# module-simple.net
KiCad netlist of a schematic drawn in EAGLE
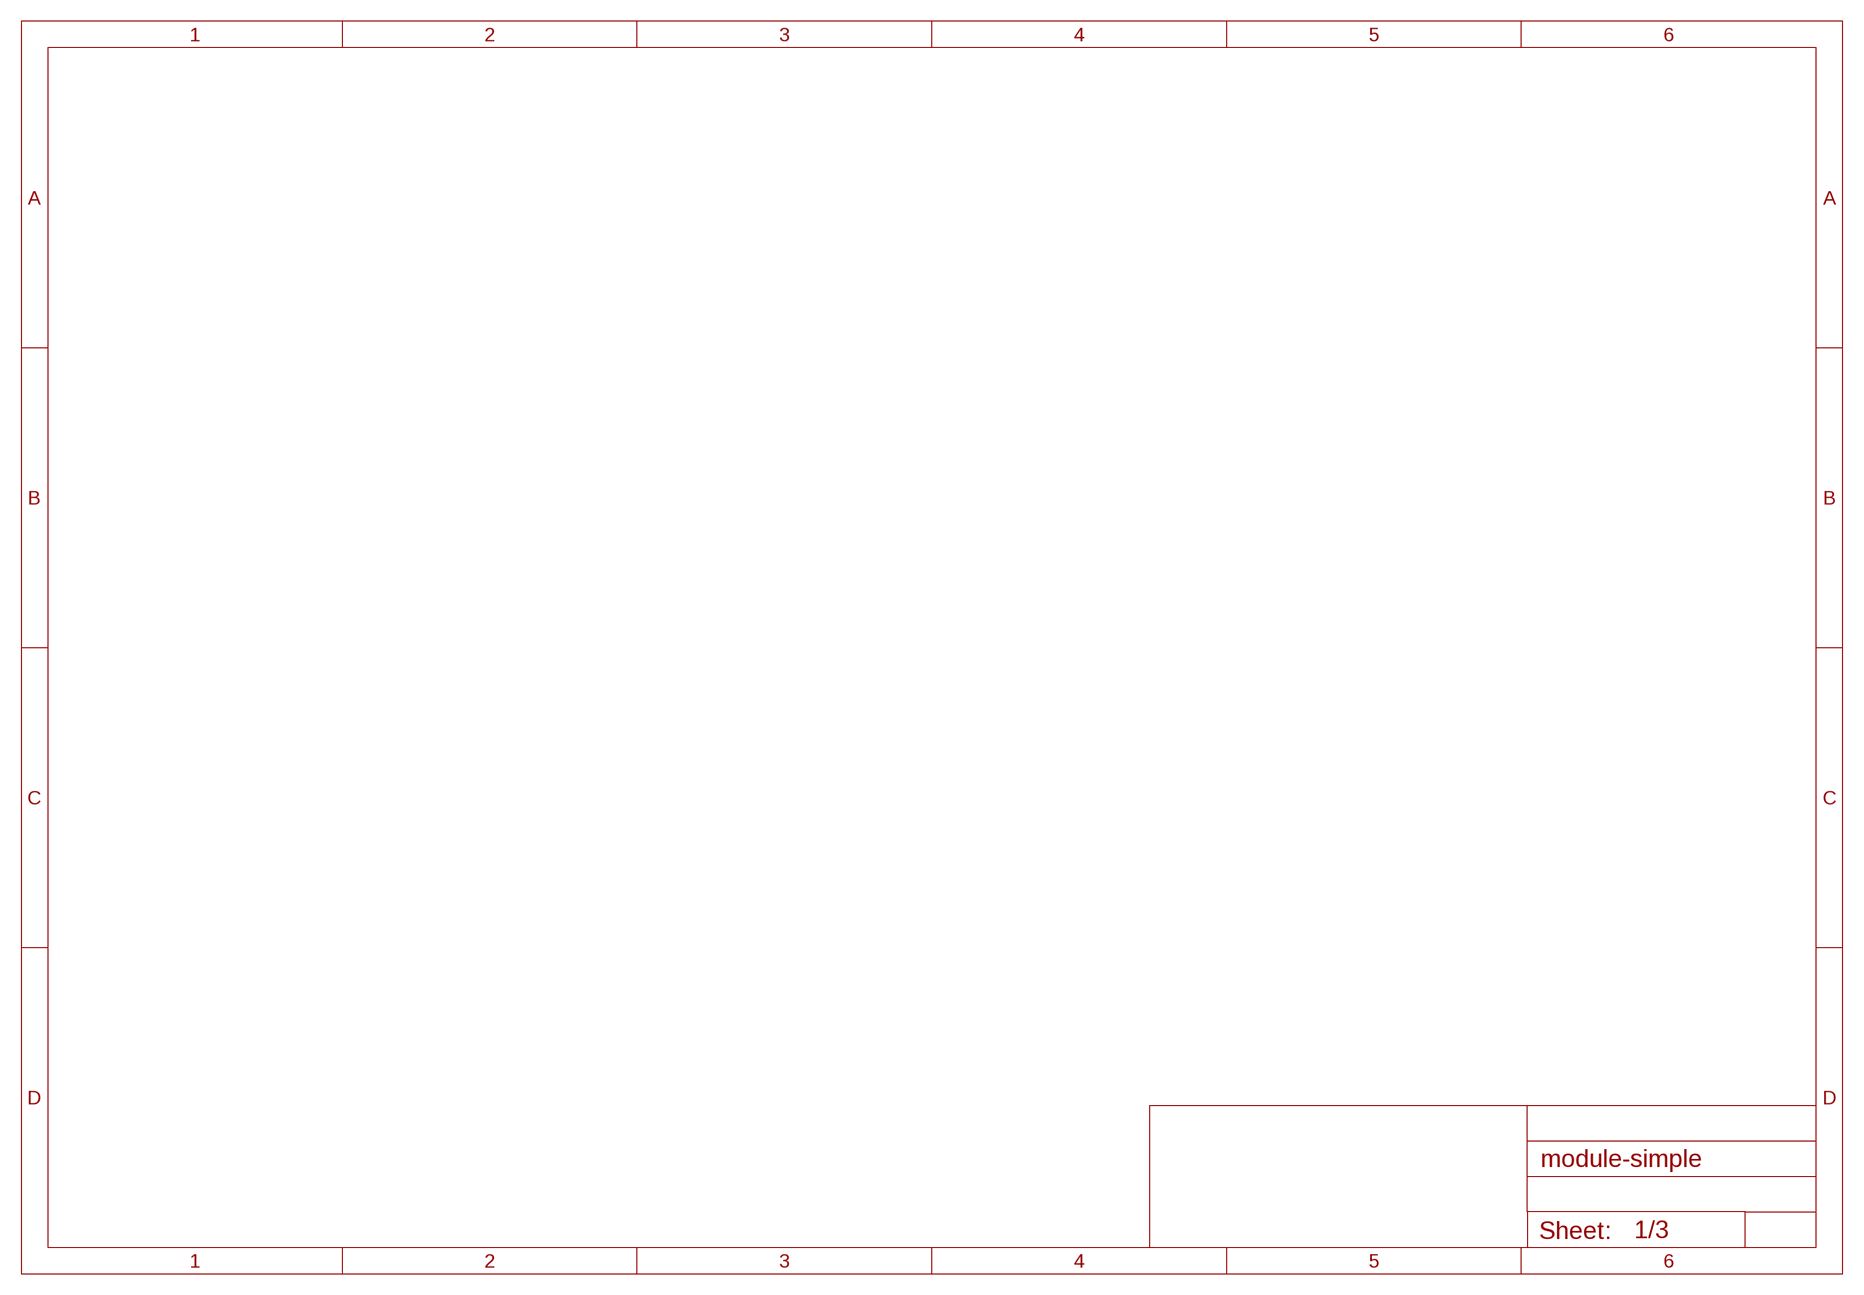
[diagram p0: schematic, sheet 1]
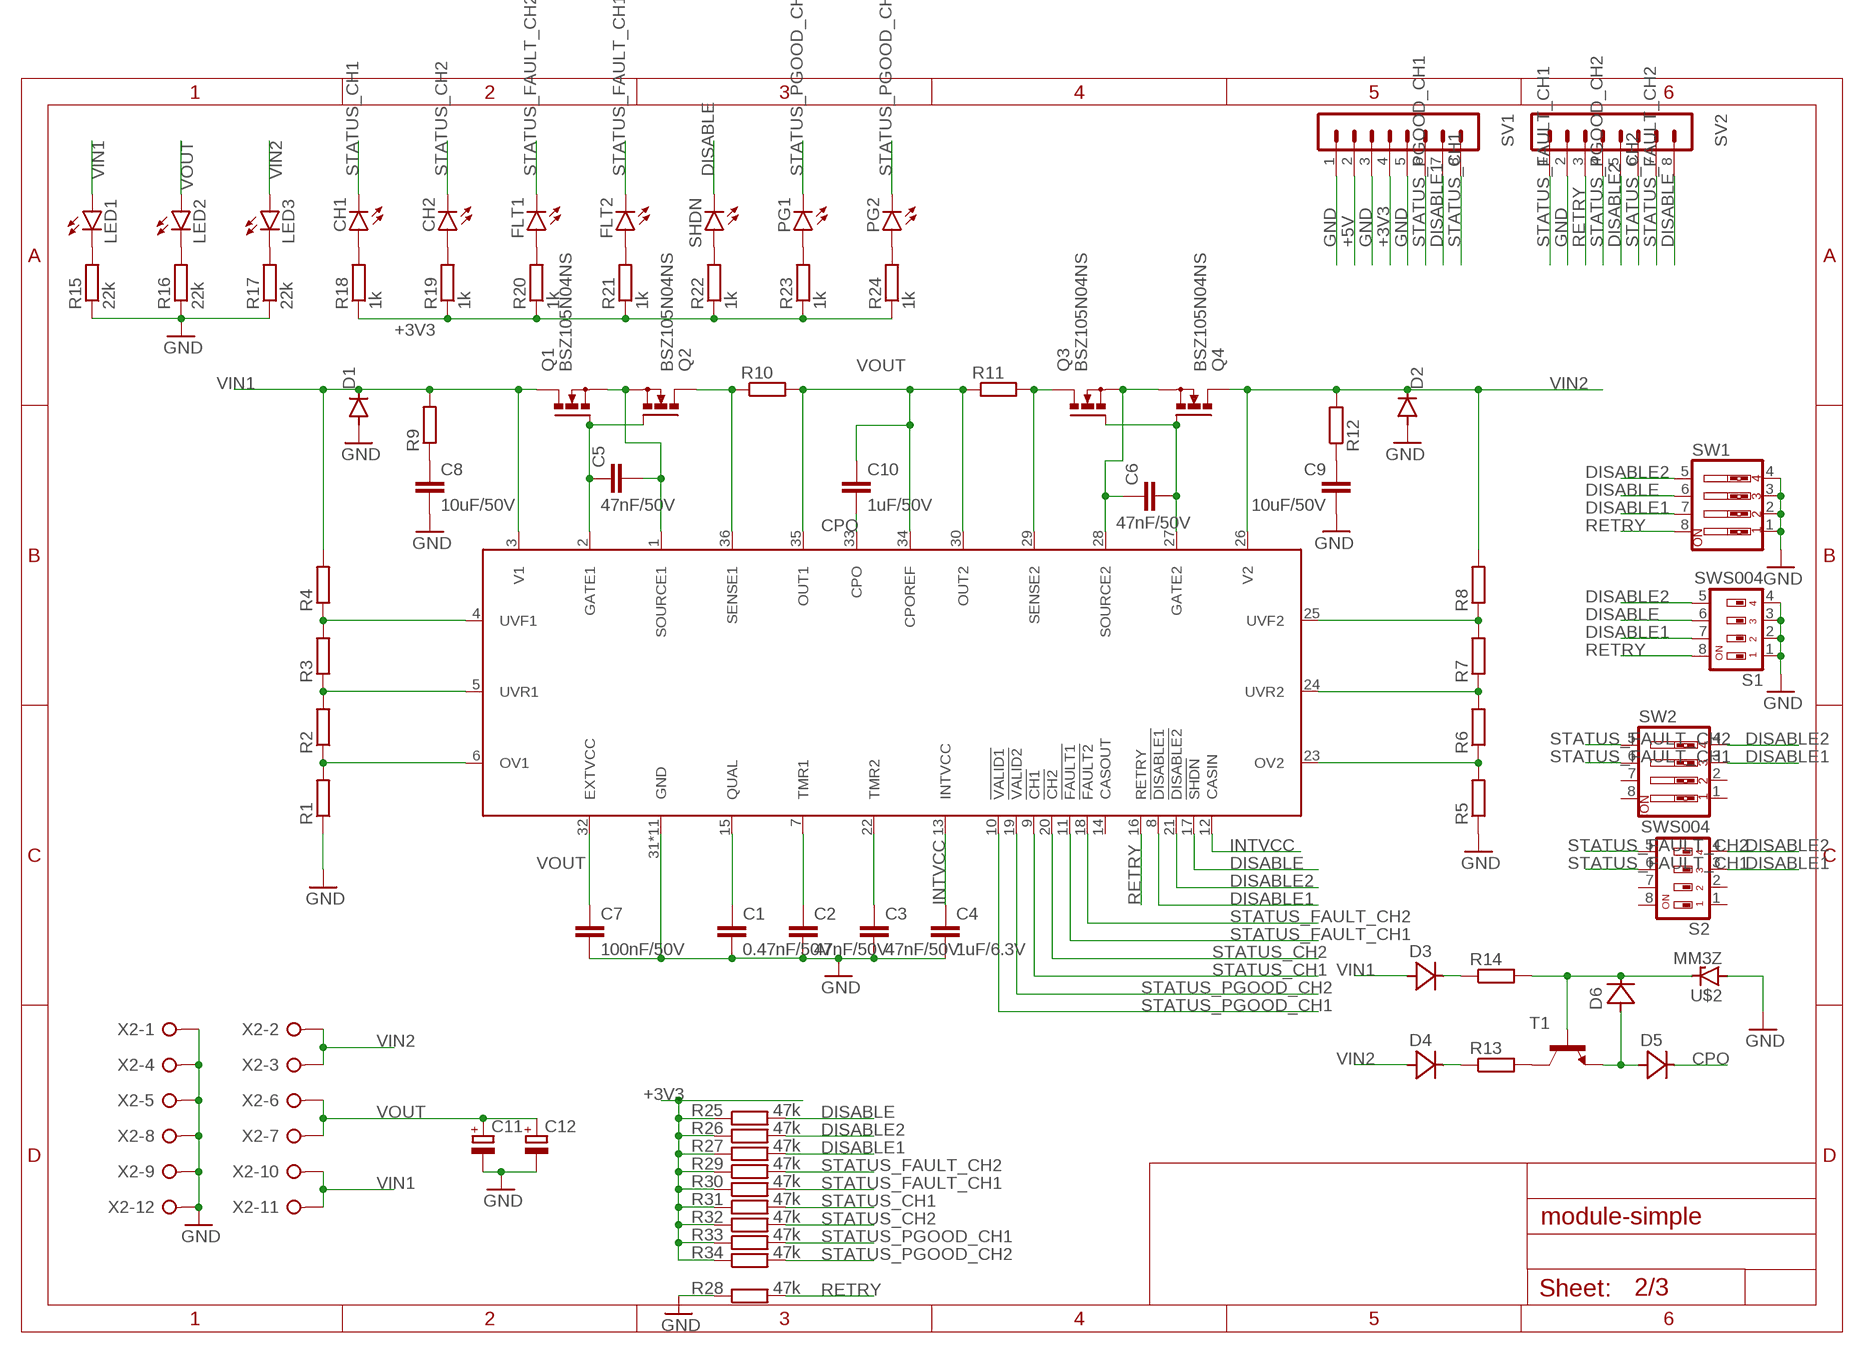
[diagram p1: schematic, sheet 2]
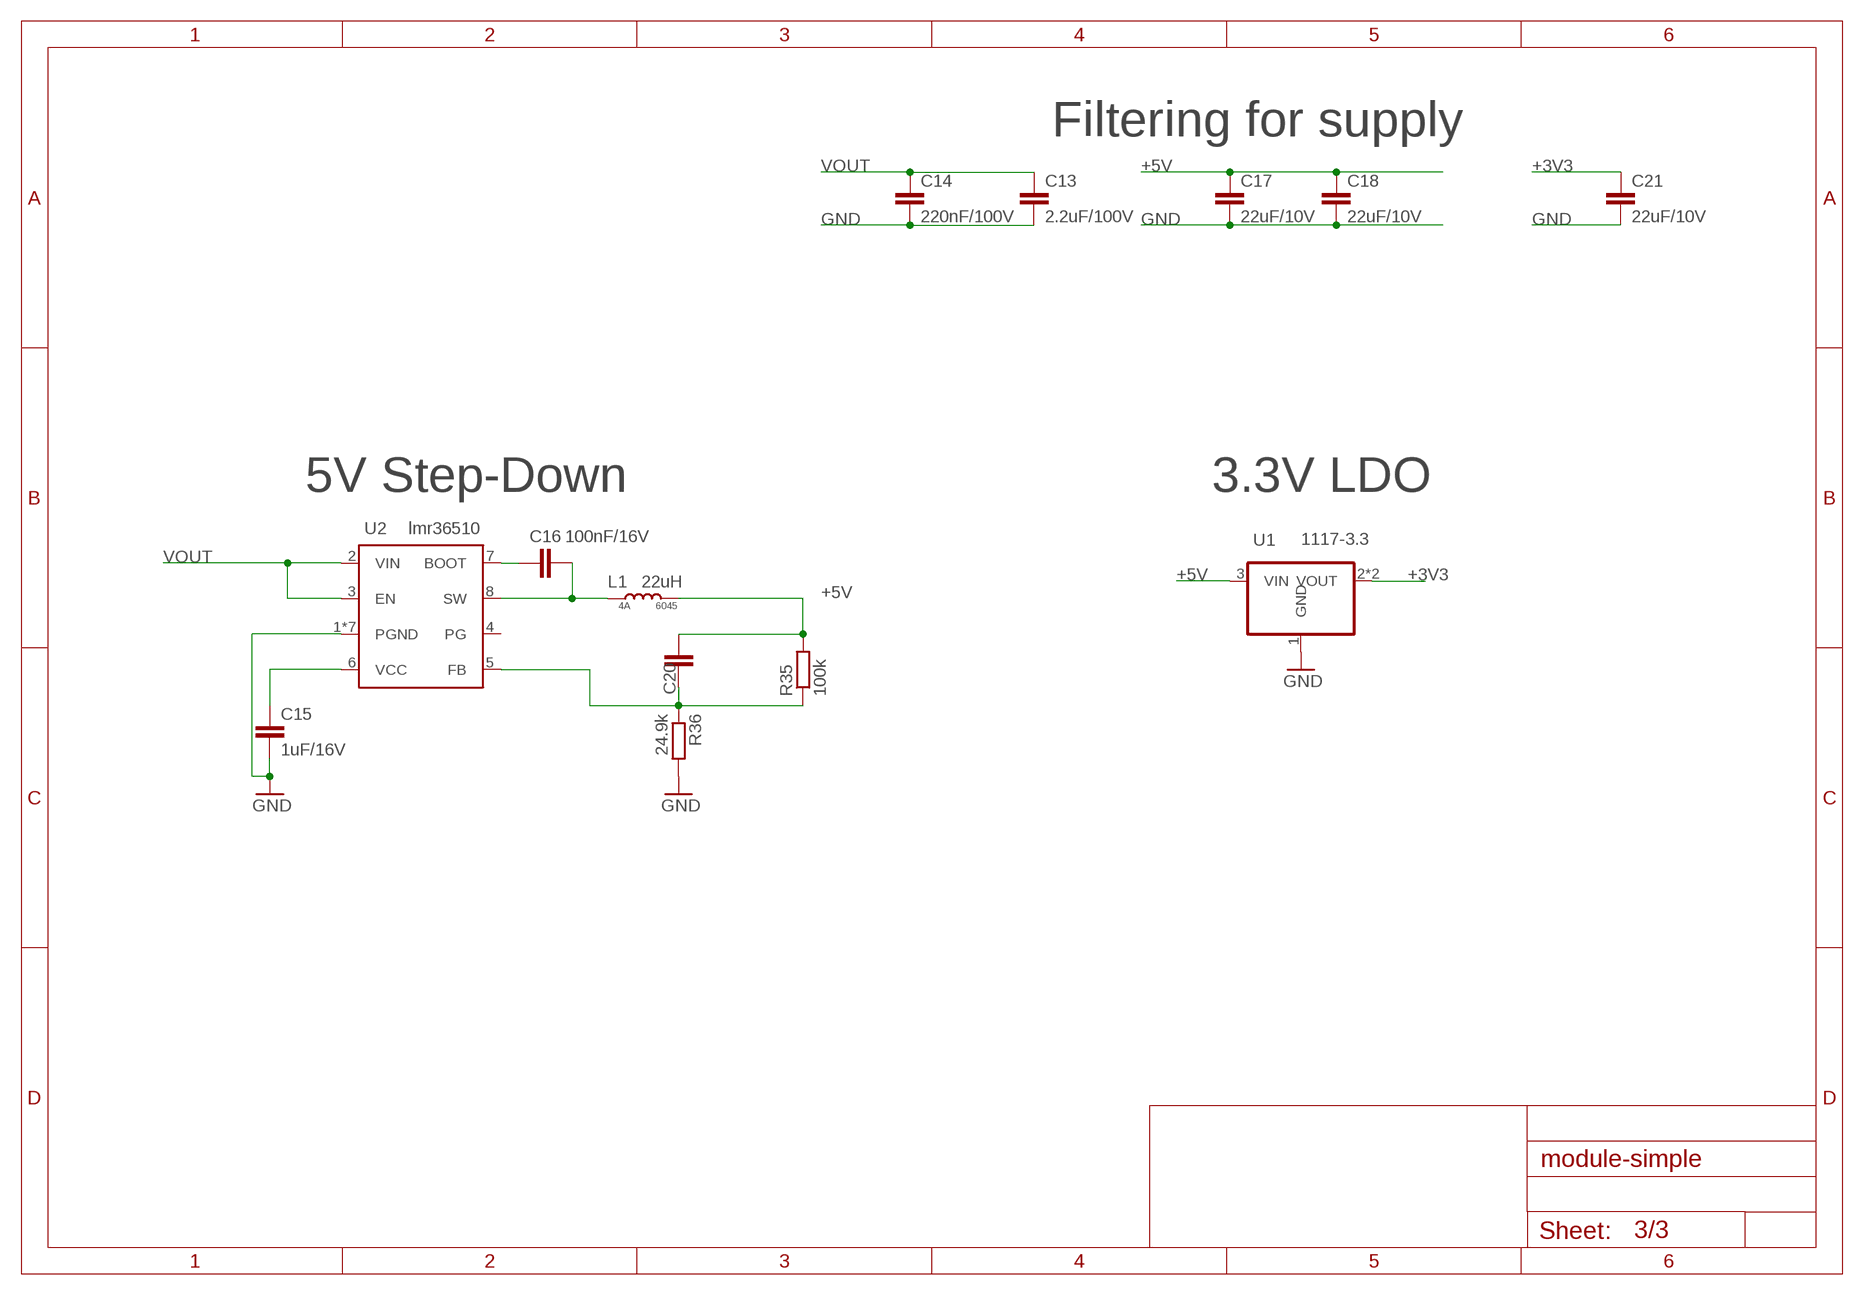
[diagram p2: schematic, sheet 3]

(export (version "E")
  (design (tool "Eeschema 10.0.6"))
  (components
    (comp (ref "C1")
      (value "0.47nF/50V")
      (footprint "eagle-import:C0603")
      (libsource (lib "eagle-import") (part "C-EUC0603"))
    )
    (comp (ref "C2")
      (value "47nF/50V")
      (footprint "eagle-import:C0603")
      (libsource (lib "eagle-import") (part "C-EUC0603"))
    )
    (comp (ref "C3")
      (value "47nF/50V")
      (footprint "eagle-import:C0603")
      (libsource (lib "eagle-import") (part "C-EUC0603"))
    )
    (comp (ref "C4")
      (value "1uF/6.3V")
      (footprint "eagle-import:C0603")
      (libsource (lib "eagle-import") (part "C-EUC0603"))
    )
    (comp (ref "C5")
      (value "47nF/50V")
      (footprint "eagle-import:C0603")
      (libsource (lib "eagle-import") (part "C-EUC0603"))
    )
    (comp (ref "C6")
      (value "47nF/50V")
      (footprint "eagle-import:C0603")
      (libsource (lib "eagle-import") (part "C-EUC0603"))
    )
    (comp (ref "C7")
      (value "100nF/50V")
      (footprint "eagle-import:C0603")
      (libsource (lib "eagle-import") (part "C-EUC0603"))
    )
    (comp (ref "C8")
      (value "10uF/50V")
      (footprint "eagle-import:C1206")
      (libsource (lib "eagle-import") (part "C-EUC1206"))
    )
    (comp (ref "C9")
      (value "10uF/50V")
      (footprint "eagle-import:C1206")
      (libsource (lib "eagle-import") (part "C-EUC1206"))
    )
    (comp (ref "C10")
      (value "1uF/50V")
      (footprint "eagle-import:C0805")
      (libsource (lib "eagle-import") (part "C-EUC0805"))
    )
    (comp (ref "C11")
      (value "CPOL-EU140CLH-1010")
      (footprint "eagle-import:140CLH-1010")
      (libsource (lib "eagle-import") (part "CPOL-EU140CLH-1010"))
    )
    (comp (ref "C12")
      (value "CPOL-EU140CLH-1010")
      (footprint "eagle-import:140CLH-1010")
      (libsource (lib "eagle-import") (part "CPOL-EU140CLH-1010"))
    )
    (comp (ref "CH1")
      (value "LEDCHIP-LED0603")
      (footprint "eagle-import:CHIP-LED0603")
      (libsource (lib "eagle-import") (part "LEDCHIP-LED0603"))
    )
    (comp (ref "CH2")
      (value "LEDCHIP-LED0603")
      (footprint "eagle-import:CHIP-LED0603")
      (libsource (lib "eagle-import") (part "LEDCHIP-LED0603"))
    )
    (comp (ref "D1")
      (value "DIODE-DO214AC")
      (footprint "eagle-import:DO214AC")
      (libsource (lib "eagle-import") (part "DIODE-DO214AC"))
    )
    (comp (ref "D2")
      (value "DIODE-DO214AC")
      (footprint "eagle-import:DO214AC")
      (libsource (lib "eagle-import") (part "DIODE-DO214AC"))
    )
    (comp (ref "D3")
      (value "1N4148WS")
      (footprint "eagle-import:SOD323")
      (libsource (lib "eagle-import") (part "1N4148WS"))
    )
    (comp (ref "D4")
      (value "1N4148WS")
      (footprint "eagle-import:SOD323")
      (libsource (lib "eagle-import") (part "1N4148WS"))
    )
    (comp (ref "D5")
      (value "1N4148WS")
      (footprint "eagle-import:SOD323")
      (libsource (lib "eagle-import") (part "1N4148WS"))
    )
    (comp (ref "D6")
      (value "1N4148WS")
      (footprint "eagle-import:SOD323")
      (libsource (lib "eagle-import") (part "1N4148WS"))
    )
    (comp (ref "FLT1")
      (value "LEDCHIP-LED0603")
      (footprint "eagle-import:CHIP-LED0603")
      (libsource (lib "eagle-import") (part "LEDCHIP-LED0603"))
    )
    (comp (ref "FLT2")
      (value "LEDCHIP-LED0603")
      (footprint "eagle-import:CHIP-LED0603")
      (libsource (lib "eagle-import") (part "LEDCHIP-LED0603"))
    )
    (comp (ref "LED1")
      (value "LEDCHIP-LED0603")
      (footprint "eagle-import:CHIP-LED0603")
      (libsource (lib "eagle-import") (part "LEDCHIP-LED0603"))
    )
    (comp (ref "LED2")
      (value "LEDCHIP-LED0603")
      (footprint "eagle-import:CHIP-LED0603")
      (libsource (lib "eagle-import") (part "LEDCHIP-LED0603"))
    )
    (comp (ref "LED3")
      (value "LEDCHIP-LED0603")
      (footprint "eagle-import:CHIP-LED0603")
      (libsource (lib "eagle-import") (part "LEDCHIP-LED0603"))
    )
    (comp (ref "PG1")
      (value "LEDCHIP-LED0603")
      (footprint "eagle-import:CHIP-LED0603")
      (libsource (lib "eagle-import") (part "LEDCHIP-LED0603"))
    )
    (comp (ref "PG2")
      (value "LEDCHIP-LED0603")
      (footprint "eagle-import:CHIP-LED0603")
      (libsource (lib "eagle-import") (part "LEDCHIP-LED0603"))
    )
    (comp (ref "Q1")
      (value "BSZ105N04NS")
      (footprint "eagle-import:PG-TDSON-8")
      (libsource (lib "eagle-import") (part "BSZ105N04NS"))
    )
    (comp (ref "Q2")
      (value "BSZ105N04NS")
      (footprint "eagle-import:PG-TDSON-8")
      (libsource (lib "eagle-import") (part "BSZ105N04NS"))
    )
    (comp (ref "Q3")
      (value "BSZ105N04NS")
      (footprint "eagle-import:PG-TDSON-8")
      (libsource (lib "eagle-import") (part "BSZ105N04NS"))
    )
    (comp (ref "Q4")
      (value "BSZ105N04NS")
      (footprint "eagle-import:PG-TDSON-8")
      (libsource (lib "eagle-import") (part "BSZ105N04NS"))
    )
    (comp (ref "R1")
      (value "R-EU_R0603")
      (footprint "eagle-import:R0603")
      (libsource (lib "eagle-import") (part "R-EU_R0603"))
    )
    (comp (ref "R2")
      (value "R-EU_R0603")
      (footprint "eagle-import:R0603")
      (libsource (lib "eagle-import") (part "R-EU_R0603"))
    )
    (comp (ref "R3")
      (value "R-EU_R0603")
      (footprint "eagle-import:R0603")
      (libsource (lib "eagle-import") (part "R-EU_R0603"))
    )
    (comp (ref "R4")
      (value "R-EU_R0603")
      (footprint "eagle-import:R0603")
      (libsource (lib "eagle-import") (part "R-EU_R0603"))
    )
    (comp (ref "R5")
      (value "R-EU_R0603")
      (footprint "eagle-import:R0603")
      (libsource (lib "eagle-import") (part "R-EU_R0603"))
    )
    (comp (ref "R6")
      (value "R-EU_R0603")
      (footprint "eagle-import:R0603")
      (libsource (lib "eagle-import") (part "R-EU_R0603"))
    )
    (comp (ref "R7")
      (value "R-EU_R0603")
      (footprint "eagle-import:R0603")
      (libsource (lib "eagle-import") (part "R-EU_R0603"))
    )
    (comp (ref "R8")
      (value "R-EU_R0603")
      (footprint "eagle-import:R0603")
      (libsource (lib "eagle-import") (part "R-EU_R0603"))
    )
    (comp (ref "R9")
      (value "R-EU_R0603")
      (footprint "eagle-import:R0603")
      (libsource (lib "eagle-import") (part "R-EU_R0603"))
    )
    (comp (ref "R10")
      (value "R-EU_R2512")
      (footprint "eagle-import:R2512")
      (libsource (lib "eagle-import") (part "R-EU_R2512"))
    )
    (comp (ref "R11")
      (value "R-EU_R2512")
      (footprint "eagle-import:R2512")
      (libsource (lib "eagle-import") (part "R-EU_R2512"))
    )
    (comp (ref "R12")
      (value "R-EU_R0603")
      (footprint "eagle-import:R0603")
      (libsource (lib "eagle-import") (part "R-EU_R0603"))
    )
    (comp (ref "R13")
      (value "R-EU_R0603")
      (footprint "eagle-import:R0603")
      (libsource (lib "eagle-import") (part "R-EU_R0603"))
    )
    (comp (ref "R14")
      (value "R-EU_R0603")
      (footprint "eagle-import:R0603")
      (libsource (lib "eagle-import") (part "R-EU_R0603"))
    )
    (comp (ref "R15")
      (value "22k")
      (footprint "eagle-import:R0603")
      (libsource (lib "eagle-import") (part "R-EU_R0603"))
    )
    (comp (ref "R16")
      (value "22k")
      (footprint "eagle-import:R0603")
      (libsource (lib "eagle-import") (part "R-EU_R0603"))
    )
    (comp (ref "R17")
      (value "22k")
      (footprint "eagle-import:R0603")
      (libsource (lib "eagle-import") (part "R-EU_R0603"))
    )
    (comp (ref "R18")
      (value "1k")
      (footprint "eagle-import:R0603")
      (libsource (lib "eagle-import") (part "R-EU_R0603"))
    )
    (comp (ref "R19")
      (value "1k")
      (footprint "eagle-import:R0603")
      (libsource (lib "eagle-import") (part "R-EU_R0603"))
    )
    (comp (ref "R20")
      (value "1k")
      (footprint "eagle-import:R0603")
      (libsource (lib "eagle-import") (part "R-EU_R0603"))
    )
    (comp (ref "R21")
      (value "1k")
      (footprint "eagle-import:R0603")
      (libsource (lib "eagle-import") (part "R-EU_R0603"))
    )
    (comp (ref "R22")
      (value "1k")
      (footprint "eagle-import:R0603")
      (libsource (lib "eagle-import") (part "R-EU_R0603"))
    )
    (comp (ref "R23")
      (value "1k")
      (footprint "eagle-import:R0603")
      (libsource (lib "eagle-import") (part "R-EU_R0603"))
    )
    (comp (ref "R24")
      (value "1k")
      (footprint "eagle-import:R0603")
      (libsource (lib "eagle-import") (part "R-EU_R0603"))
    )
    (comp (ref "R25")
      (value "47k")
      (footprint "eagle-import:R0603")
      (libsource (lib "eagle-import") (part "R-EU_R0603"))
    )
    (comp (ref "R26")
      (value "47k")
      (footprint "eagle-import:R0603")
      (libsource (lib "eagle-import") (part "R-EU_R0603"))
    )
    (comp (ref "R27")
      (value "47k")
      (footprint "eagle-import:R0603")
      (libsource (lib "eagle-import") (part "R-EU_R0603"))
    )
    (comp (ref "R28")
      (value "47k")
      (footprint "eagle-import:R0603")
      (libsource (lib "eagle-import") (part "R-EU_R0603"))
    )
    (comp (ref "R29")
      (value "47k")
      (footprint "eagle-import:R0603")
      (libsource (lib "eagle-import") (part "R-EU_R0603"))
    )
    (comp (ref "R30")
      (value "47k")
      (footprint "eagle-import:R0603")
      (libsource (lib "eagle-import") (part "R-EU_R0603"))
    )
    (comp (ref "R31")
      (value "47k")
      (footprint "eagle-import:R0603")
      (libsource (lib "eagle-import") (part "R-EU_R0603"))
    )
    (comp (ref "R32")
      (value "47k")
      (footprint "eagle-import:R0603")
      (libsource (lib "eagle-import") (part "R-EU_R0603"))
    )
    (comp (ref "R33")
      (value "47k")
      (footprint "eagle-import:R0603")
      (libsource (lib "eagle-import") (part "R-EU_R0603"))
    )
    (comp (ref "R34")
      (value "47k")
      (footprint "eagle-import:R0603")
      (libsource (lib "eagle-import") (part "R-EU_R0603"))
    )
    (comp (ref "S1")
      (value "SWS004")
      (footprint "eagle-import:SMS-004")
      (libsource (lib "eagle-import") (part "SWS004"))
    )
    (comp (ref "S2")
      (value "SWS004")
      (footprint "eagle-import:SMS-004")
      (libsource (lib "eagle-import") (part "SWS004"))
    )
    (comp (ref "SHDN")
      (value "LEDCHIP-LED0603")
      (footprint "eagle-import:CHIP-LED0603")
      (libsource (lib "eagle-import") (part "LEDCHIP-LED0603"))
    )
    (comp (ref "SV1")
      (value "MA08-1")
      (footprint "eagle-import:MA08-1")
      (libsource (lib "eagle-import") (part "MA08-1"))
    )
    (comp (ref "SV2")
      (value "MA08-1")
      (footprint "eagle-import:MA08-1")
      (libsource (lib "eagle-import") (part "MA08-1"))
    )
    (comp (ref "SW1")
      (value "SW_DIP-4")
      (footprint "eagle-import:EDG-04")
      (libsource (lib "eagle-import") (part "SW_DIP-4"))
    )
    (comp (ref "SW2")
      (value "SW_DIP-4")
      (footprint "eagle-import:EDG-04")
      (libsource (lib "eagle-import") (part "SW_DIP-4"))
    )
    (comp (ref "T1")
      (value "MMBT2222ALT1-NPN-SOT23-BEC")
      (footprint "eagle-import:SOT23-BEC")
      (libsource (lib "eagle-import") (part "-NPN-SOT23-BECMMBT2222ALT1"))
    )
    (comp (ref "U$1")
      (value "LTC4421")
      (footprint "eagle-import:QFN50P600X500X75-37T460X360N")
      (libsource (lib "eagle-import") (part "LTC4421"))
    )
    (comp (ref "U$2")
      (value "MM3Z")
      (footprint "eagle-import:SOD323")
      (libsource (lib "eagle-import") (part "MM3Z"))
    )
    (comp (ref "X2")
      (value "W237-12P")
      (footprint "eagle-import:W237-12P")
      (libsource (lib "eagle-import") (part "W237-12P"))
    )
    (comp (ref "C13")
      (value "2.2uF/100V")
      (footprint "eagle-import:C1210")
      (libsource (lib "eagle-import") (part "C-EUC1210"))
    )
    (comp (ref "C14")
      (value "220nF/100V")
      (footprint "eagle-import:C1210")
      (libsource (lib "eagle-import") (part "C-EUC1210"))
    )
    (comp (ref "C15")
      (value "1uF/16V")
      (footprint "eagle-import:C0805")
      (libsource (lib "eagle-import") (part "C-EUC0805"))
    )
    (comp (ref "C16")
      (value "100nF/16V")
      (footprint "eagle-import:C0805")
      (libsource (lib "eagle-import") (part "C-EUC0805"))
    )
    (comp (ref "C17")
      (value "22uF/10V")
      (footprint "eagle-import:C1210")
      (libsource (lib "eagle-import") (part "C-EUC1210"))
    )
    (comp (ref "C18")
      (value "22uF/10V")
      (footprint "eagle-import:C1210")
      (libsource (lib "eagle-import") (part "C-EUC1210"))
    )
    (comp (ref "C20")
      (value "C-EUC0603")
      (footprint "eagle-import:C0603")
      (libsource (lib "eagle-import") (part "C-EUC0603"))
    )
    (comp (ref "C21")
      (value "22uF/10V")
      (footprint "eagle-import:C1210")
      (libsource (lib "eagle-import") (part "C-EUC1210"))
    )
    (comp (ref "L1")
      (value "22uH")
      (footprint "eagle-import:DJNR6045")
      (fields (field (name "PACKAGE") "6045") (field (name "CURRENT") "4A"))
      (libsource (lib "eagle-import") (part "DJNR6045"))
    )
    (comp (ref "R35")
      (value "100k")
      (footprint "eagle-import:R0603")
      (libsource (lib "eagle-import") (part "R-EU_R0603"))
    )
    (comp (ref "R36")
      (value "24.9k")
      (footprint "eagle-import:R0603")
      (libsource (lib "eagle-import") (part "R-EU_R0603"))
    )
    (comp (ref "U1")
      (value "1117-3.3")
      (footprint "eagle-import:SOT230P700X180-4")
      (libsource (lib "eagle-import") (part "LD1117S50"))
    )
    (comp (ref "U2")
      (value "lmr36510")
      (footprint "eagle-import:SOIC127P600X170-9T240X310N")
      (libsource (lib "eagle-import") (part "LMR36510"))
    )
  )
  (nets
    (net (code "1") (name "+3V3") (class "Default")
      (node (ref "C21") (pin "1") (pinfunction "1_1") (pintype "passive"))
      (node (ref "R18") (pin "1") (pinfunction "1_1") (pintype "passive"))
      (node (ref "R19") (pin "1") (pinfunction "1_1") (pintype "passive"))
      (node (ref "R20") (pin "1") (pinfunction "1_1") (pintype "passive"))
      (node (ref "R21") (pin "1") (pinfunction "1_1") (pintype "passive"))
      (node (ref "R22") (pin "1") (pinfunction "1_1") (pintype "passive"))
      (node (ref "R23") (pin "1") (pinfunction "1_1") (pintype "passive"))
      (node (ref "R24") (pin "1") (pinfunction "1_1") (pintype "passive"))
      (node (ref "R25") (pin "1") (pinfunction "1_1") (pintype "passive"))
      (node (ref "R26") (pin "1") (pinfunction "1_1") (pintype "passive"))
      (node (ref "R27") (pin "1") (pinfunction "1_1") (pintype "passive"))
      (node (ref "R29") (pin "1") (pinfunction "1_1") (pintype "passive"))
      (node (ref "R30") (pin "1") (pinfunction "1_1") (pintype "passive"))
      (node (ref "R31") (pin "1") (pinfunction "1_1") (pintype "passive"))
      (node (ref "R32") (pin "1") (pinfunction "1_1") (pintype "passive"))
      (node (ref "R33") (pin "1") (pinfunction "1_1") (pintype "passive"))
      (node (ref "R34") (pin "1") (pinfunction "1_1") (pintype "passive"))
      (node (ref "SV1") (pin "4") (pinfunction "4_4") (pintype "passive"))
      (node (ref "U1") (pin "2") (pinfunction "VOUT_2") (pintype "output"))
      (node (ref "U1") (pin "4") (pinfunction "VOUT_4") (pintype "output"))
    )
    (net (code "2") (name "+5V") (class "Default")
      (node (ref "C17") (pin "1") (pinfunction "1_1") (pintype "passive"))
      (node (ref "C18") (pin "1") (pinfunction "1_1") (pintype "passive"))
      (node (ref "C20") (pin "2") (pinfunction "2_2") (pintype "passive"))
      (node (ref "L1") (pin "P$2") (pinfunction "2_P$2") (pintype "passive"))
      (node (ref "R35") (pin "2") (pinfunction "2_2") (pintype "passive"))
      (node (ref "SV1") (pin "2") (pinfunction "2_2") (pintype "passive"))
      (node (ref "U1") (pin "3") (pinfunction "VIN_3") (pintype "input"))
    )
    (net (code "3") (name "CPO") (class "Default")
      (node (ref "C10") (pin "2") (pinfunction "2_2") (pintype "passive"))
      (node (ref "D5") (pin "K") (pinfunction "C_K") (pintype "passive"))
      (node (ref "U$1") (pin "33") (pinfunction "CPO_33") (pintype "bidirectional"))
    )
    (net (code "4") (name "DISABLE") (class "Default")
      (node (ref "R25") (pin "2") (pinfunction "2_2") (pintype "passive"))
      (node (ref "S1") (pin "6") (pinfunction "6_6") (pintype "passive"))
      (node (ref "SHDN") (pin "C") (pinfunction "C_C") (pintype "passive"))
      (node (ref "SV2") (pin "8") (pinfunction "8_8") (pintype "passive"))
      (node (ref "SW1") (pin "6") (pinfunction "6_6") (pintype "passive"))
      (node (ref "U$1") (pin "17") (pinfunction "~{SHDN}_17") (pintype "bidirectional"))
    )
    (net (code "5") (name "DISABLE1") (class "Default")
      (node (ref "R27") (pin "2") (pinfunction "2_2") (pintype "passive"))
      (node (ref "S1") (pin "7") (pinfunction "7_7") (pintype "passive"))
      (node (ref "S2") (pin "3") (pinfunction "3_3") (pintype "passive"))
      (node (ref "SV1") (pin "7") (pinfunction "7_7") (pintype "passive"))
      (node (ref "SW1") (pin "7") (pinfunction "7_7") (pintype "passive"))
      (node (ref "SW2") (pin "3") (pinfunction "3_3") (pintype "passive"))
      (node (ref "U$1") (pin "8") (pinfunction "~{DISABLE1}_8") (pintype "bidirectional"))
    )
    (net (code "6") (name "DISABLE2") (class "Default")
      (node (ref "R26") (pin "2") (pinfunction "2_2") (pintype "passive"))
      (node (ref "S1") (pin "5") (pinfunction "5_5") (pintype "passive"))
      (node (ref "S2") (pin "4") (pinfunction "4_4") (pintype "passive"))
      (node (ref "SV2") (pin "5") (pinfunction "5_5") (pintype "passive"))
      (node (ref "SW1") (pin "5") (pinfunction "5_5") (pintype "passive"))
      (node (ref "SW2") (pin "4") (pinfunction "4_4") (pintype "passive"))
      (node (ref "U$1") (pin "21") (pinfunction "~{DISABLE2}_21") (pintype "bidirectional"))
    )
    (net (code "7") (name "GND") (class "Default")
      (node (ref "C1") (pin "2") (pinfunction "2_2") (pintype "passive"))
      (node (ref "C11") (pin "-") (pinfunction "-_-") (pintype "passive"))
      (node (ref "C12") (pin "-") (pinfunction "-_-") (pintype "passive"))
      (node (ref "C13") (pin "2") (pinfunction "2_2") (pintype "passive"))
      (node (ref "C14") (pin "2") (pinfunction "2_2") (pintype "passive"))
      (node (ref "C15") (pin "2") (pinfunction "2_2") (pintype "passive"))
      (node (ref "C17") (pin "2") (pinfunction "2_2") (pintype "passive"))
      (node (ref "C18") (pin "2") (pinfunction "2_2") (pintype "passive"))
      (node (ref "C2") (pin "2") (pinfunction "2_2") (pintype "passive"))
      (node (ref "C21") (pin "2") (pinfunction "2_2") (pintype "passive"))
      (node (ref "C3") (pin "2") (pinfunction "2_2") (pintype "passive"))
      (node (ref "C4") (pin "2") (pinfunction "2_2") (pintype "passive"))
      (node (ref "C7") (pin "2") (pinfunction "2_2") (pintype "passive"))
      (node (ref "C8") (pin "2") (pinfunction "2_2") (pintype "passive"))
      (node (ref "C9") (pin "2") (pinfunction "2_2") (pintype "passive"))
      (node (ref "D1") (pin "A") (pinfunction "A_A") (pintype "passive"))
      (node (ref "D2") (pin "A") (pinfunction "A_A") (pintype "passive"))
      (node (ref "R1") (pin "1") (pinfunction "1_1") (pintype "passive"))
      (node (ref "R15") (pin "1") (pinfunction "1_1") (pintype "passive"))
      (node (ref "R16") (pin "1") (pinfunction "1_1") (pintype "passive"))
      (node (ref "R17") (pin "1") (pinfunction "1_1") (pintype "passive"))
      (node (ref "R28") (pin "1") (pinfunction "1_1") (pintype "passive"))
      (node (ref "R36") (pin "2") (pinfunction "2_2") (pintype "passive"))
      (node (ref "R5") (pin "1") (pinfunction "1_1") (pintype "passive"))
      (node (ref "S1") (pin "1") (pinfunction "1_1") (pintype "passive"))
      (node (ref "S1") (pin "2") (pinfunction "2_2") (pintype "passive"))
      (node (ref "S1") (pin "3") (pinfunction "3_3") (pintype "passive"))
      (node (ref "S1") (pin "4") (pinfunction "4_4") (pintype "passive"))
      (node (ref "SV1") (pin "1") (pinfunction "1_1") (pintype "passive"))
      (node (ref "SV1") (pin "3") (pinfunction "3_3") (pintype "passive"))
      (node (ref "SV1") (pin "5") (pinfunction "5_5") (pintype "passive"))
      (node (ref "SV2") (pin "2") (pinfunction "2_2") (pintype "passive"))
      (node (ref "SW1") (pin "1") (pinfunction "1_1") (pintype "passive"))
      (node (ref "SW1") (pin "2") (pinfunction "2_2") (pintype "passive"))
      (node (ref "SW1") (pin "3") (pinfunction "3_3") (pintype "passive"))
      (node (ref "SW1") (pin "4") (pinfunction "4_4") (pintype "passive"))
      (node (ref "U$1") (pin "31") (pinfunction "GND_31") (pintype "bidirectional"))
      (node (ref "U$1") (pin "37") (pinfunction "GND_37") (pintype "bidirectional"))
      (node (ref "U$1") (pin "P$1") (pinfunction "GND_P$1") (pintype "bidirectional"))
      (node (ref "U$1") (pin "P$2") (pinfunction "GND_P$2") (pintype "bidirectional"))
      (node (ref "U$1") (pin "P$3") (pinfunction "GND_P$3") (pintype "bidirectional"))
      (node (ref "U$1") (pin "P$4") (pinfunction "GND_P$4") (pintype "bidirectional"))
      (node (ref "U$1") (pin "P$5") (pinfunction "GND_P$5") (pintype "bidirectional"))
      (node (ref "U$1") (pin "P$6") (pinfunction "GND_P$6") (pintype "bidirectional"))
      (node (ref "U$1") (pin "P$7") (pinfunction "GND_P$7") (pintype "bidirectional"))
      (node (ref "U$1") (pin "P$8") (pinfunction "GND_P$8") (pintype "bidirectional"))
      (node (ref "U$1") (pin "P$9") (pinfunction "GND_P$9") (pintype "bidirectional"))
      (node (ref "U$2") (pin "A") (pinfunction "A_A") (pintype "passive"))
      (node (ref "U1") (pin "1") (pinfunction "GND_1") (pintype "power_in"))
      (node (ref "U2") (pin "1") (pinfunction "PGND_1") (pintype "bidirectional"))
      (node (ref "U2") (pin "9") (pinfunction "PGND_9") (pintype "bidirectional"))
      (node (ref "U2") (pin "P$1") (pinfunction "PGND_P$1") (pintype "bidirectional"))
      (node (ref "U2") (pin "P$2") (pinfunction "PGND_P$2") (pintype "bidirectional"))
      (node (ref "U2") (pin "P$3") (pinfunction "PGND_P$3") (pintype "bidirectional"))
      (node (ref "U2") (pin "P$4") (pinfunction "PGND_P$4") (pintype "bidirectional"))
      (node (ref "U2") (pin "P$5") (pinfunction "PGND_P$5") (pintype "bidirectional"))
      (node (ref "X2") (pin "1") (pinfunction "KL_1") (pintype "passive"))
      (node (ref "X2") (pin "12") (pinfunction "KL_12") (pintype "passive"))
      (node (ref "X2") (pin "4") (pinfunction "KL_4") (pintype "passive"))
      (node (ref "X2") (pin "5") (pinfunction "KL_5") (pintype "passive"))
      (node (ref "X2") (pin "8") (pinfunction "KL_8") (pintype "passive"))
      (node (ref "X2") (pin "9") (pinfunction "KL_9") (pintype "passive"))
    )
    (net (code "8") (name "INTVCC") (class "Default")
      (node (ref "C4") (pin "1") (pinfunction "1_1") (pintype "passive"))
      (node (ref "U$1") (pin "12") (pinfunction "CASIN_12") (pintype "bidirectional"))
      (node (ref "U$1") (pin "13") (pinfunction "INTVCC_13") (pintype "bidirectional"))
    )
    (net (code "9") (name "Net-(C8-Pad1)") (class "Default")
      (node (ref "C8") (pin "1") (pinfunction "1_1") (pintype "passive"))
      (node (ref "R9") (pin "1") (pinfunction "1_1") (pintype "passive"))
    )
    (net (code "10") (name "Net-(C9-Pad1)") (class "Default")
      (node (ref "C9") (pin "1") (pinfunction "1_1") (pintype "passive"))
      (node (ref "R12") (pin "1") (pinfunction "1_1") (pintype "passive"))
    )
    (net (code "11") (name "Net-(CH1-PadA)") (class "Default")
      (node (ref "CH1") (pin "A") (pinfunction "A_A") (pintype "passive"))
      (node (ref "R18") (pin "2") (pinfunction "2_2") (pintype "passive"))
    )
    (net (code "12") (name "Net-(CH2-PadA)") (class "Default")
      (node (ref "CH2") (pin "A") (pinfunction "A_A") (pintype "passive"))
      (node (ref "R19") (pin "2") (pinfunction "2_2") (pintype "passive"))
    )
    (net (code "13") (name "Net-(D3-C)") (class "Default")
      (node (ref "D3") (pin "K") (pinfunction "C_K") (pintype "passive"))
      (node (ref "R14") (pin "1") (pinfunction "1_1") (pintype "passive"))
    )
    (net (code "14") (name "Net-(D4-C)") (class "Default")
      (node (ref "D4") (pin "K") (pinfunction "C_K") (pintype "passive"))
      (node (ref "R13") (pin "1") (pinfunction "1_1") (pintype "passive"))
    )
    (net (code "15") (name "Net-(D5-PadA)") (class "Default")
      (node (ref "D5") (pin "A") (pinfunction "A_A") (pintype "passive"))
      (node (ref "D6") (pin "A") (pinfunction "A_A") (pintype "passive"))
      (node (ref "T1") (pin "E") (pinfunction "E_E") (pintype "passive"))
    )
    (net (code "16") (name "Net-(D6-C)") (class "Default")
      (node (ref "D6") (pin "K") (pinfunction "C_K") (pintype "passive"))
      (node (ref "R14") (pin "2") (pinfunction "2_2") (pintype "passive"))
      (node (ref "T1") (pin "B") (pinfunction "B_B") (pintype "passive"))
      (node (ref "U$2") (pin "K") (pinfunction "K_K") (pintype "passive"))
    )
    (net (code "17") (name "Net-(FLT1-PadA)") (class "Default")
      (node (ref "FLT1") (pin "A") (pinfunction "A_A") (pintype "passive"))
      (node (ref "R20") (pin "2") (pinfunction "2_2") (pintype "passive"))
    )
    (net (code "18") (name "Net-(FLT2-PadA)") (class "Default")
      (node (ref "FLT2") (pin "A") (pinfunction "A_A") (pintype "passive"))
      (node (ref "R21") (pin "2") (pinfunction "2_2") (pintype "passive"))
    )
    (net (code "19") (name "Net-(L1-1)") (class "Default")
      (node (ref "C16") (pin "2") (pinfunction "2_2") (pintype "passive"))
      (node (ref "L1") (pin "P$1") (pinfunction "1_P$1") (pintype "passive"))
      (node (ref "U2") (pin "8") (pinfunction "SW_8") (pintype "bidirectional"))
    )
    (net (code "20") (name "Net-(LED1-PadC)") (class "Default")
      (node (ref "LED1") (pin "C") (pinfunction "C_C") (pintype "passive"))
      (node (ref "R15") (pin "2") (pinfunction "2_2") (pintype "passive"))
    )
    (net (code "21") (name "Net-(LED2-PadC)") (class "Default")
      (node (ref "LED2") (pin "C") (pinfunction "C_C") (pintype "passive"))
      (node (ref "R16") (pin "2") (pinfunction "2_2") (pintype "passive"))
    )
    (net (code "22") (name "Net-(LED3-PadC)") (class "Default")
      (node (ref "LED3") (pin "C") (pinfunction "C_C") (pintype "passive"))
      (node (ref "R17") (pin "2") (pinfunction "2_2") (pintype "passive"))
    )
    (net (code "23") (name "Net-(PG1-PadA)") (class "Default")
      (node (ref "PG1") (pin "A") (pinfunction "A_A") (pintype "passive"))
      (node (ref "R23") (pin "2") (pinfunction "2_2") (pintype "passive"))
    )
    (net (code "24") (name "Net-(PG2-PadA)") (class "Default")
      (node (ref "PG2") (pin "A") (pinfunction "A_A") (pintype "passive"))
      (node (ref "R24") (pin "2") (pinfunction "2_2") (pintype "passive"))
    )
    (net (code "25") (name "Net-(Q1-G)") (class "Default")
      (node (ref "C5") (pin "1") (pinfunction "1_1") (pintype "passive"))
      (node (ref "Q1") (pin "4") (pinfunction "G_4") (pintype "passive"))
      (node (ref "Q2") (pin "4") (pinfunction "G_4") (pintype "passive"))
      (node (ref "U$1") (pin "2") (pinfunction "GATE1_2") (pintype "bidirectional"))
    )
    (net (code "26") (name "Net-(Q3-G)") (class "Default")
      (node (ref "C6") (pin "2") (pinfunction "2_2") (pintype "passive"))
      (node (ref "Q3") (pin "4") (pinfunction "G_4") (pintype "passive"))
      (node (ref "Q4") (pin "4") (pinfunction "G_4") (pintype "passive"))
      (node (ref "U$1") (pin "27") (pinfunction "GATE2_27") (pintype "bidirectional"))
    )
    (net (code "27") (name "Net-(R13-Pad2)") (class "Default")
      (node (ref "R13") (pin "2") (pinfunction "2_2") (pintype "passive"))
      (node (ref "T1") (pin "C") (pinfunction "C_C") (pintype "passive"))
    )
    (net (code "28") (name "Net-(R22-Pad2)") (class "Default")
      (node (ref "R22") (pin "2") (pinfunction "2_2") (pintype "passive"))
      (node (ref "SHDN") (pin "A") (pinfunction "A_A") (pintype "passive"))
    )
    (net (code "29") (name "Net-(U$1-OV1)") (class "Default")
      (node (ref "R1") (pin "2") (pinfunction "2_2") (pintype "passive"))
      (node (ref "R2") (pin "1") (pinfunction "1_1") (pintype "passive"))
      (node (ref "U$1") (pin "6") (pinfunction "OV1_6") (pintype "bidirectional"))
    )
    (net (code "30") (name "Net-(U$1-OV2)") (class "Default")
      (node (ref "R5") (pin "2") (pinfunction "2_2") (pintype "passive"))
      (node (ref "R6") (pin "1") (pinfunction "1_1") (pintype "passive"))
      (node (ref "U$1") (pin "23") (pinfunction "OV2_23") (pintype "bidirectional"))
    )
    (net (code "31") (name "Net-(U$1-QUAL)") (class "Default")
      (node (ref "C1") (pin "1") (pinfunction "1_1") (pintype "passive"))
      (node (ref "U$1") (pin "15") (pinfunction "QUAL_15") (pintype "bidirectional"))
    )
    (net (code "32") (name "Net-(U$1-SENSE1)") (class "Default")
      (node (ref "Q2") (pin "5") (pinfunction "D_5") (pintype "passive"))
      (node (ref "Q2") (pin "6") (pinfunction "D_6") (pintype "passive"))
      (node (ref "Q2") (pin "7") (pinfunction "D_7") (pintype "passive"))
      (node (ref "Q2") (pin "8") (pinfunction "D_8") (pintype "passive"))
      (node (ref "Q2") (pin "TH") (pinfunction "D_TH") (pintype "passive"))
      (node (ref "R10") (pin "1") (pinfunction "1_1") (pintype "passive"))
      (node (ref "U$1") (pin "36") (pinfunction "SENSE1_36") (pintype "bidirectional"))
    )
    (net (code "33") (name "Net-(U$1-SENSE2)") (class "Default")
      (node (ref "Q3") (pin "5") (pinfunction "D_5") (pintype "passive"))
      (node (ref "Q3") (pin "6") (pinfunction "D_6") (pintype "passive"))
      (node (ref "Q3") (pin "7") (pinfunction "D_7") (pintype "passive"))
      (node (ref "Q3") (pin "8") (pinfunction "D_8") (pintype "passive"))
      (node (ref "Q3") (pin "TH") (pinfunction "D_TH") (pintype "passive"))
      (node (ref "R11") (pin "2") (pinfunction "2_2") (pintype "passive"))
      (node (ref "U$1") (pin "29") (pinfunction "SENSE2_29") (pintype "bidirectional"))
    )
    (net (code "34") (name "Net-(U$1-SOURCE1)") (class "Default")
      (node (ref "C5") (pin "2") (pinfunction "2_2") (pintype "passive"))
      (node (ref "Q1") (pin "1") (pinfunction "S_1") (pintype "passive"))
      (node (ref "Q1") (pin "2") (pinfunction "S_2") (pintype "passive"))
      (node (ref "Q1") (pin "3") (pinfunction "S_3") (pintype "passive"))
      (node (ref "Q2") (pin "1") (pinfunction "S_1") (pintype "passive"))
      (node (ref "Q2") (pin "2") (pinfunction "S_2") (pintype "passive"))
      (node (ref "Q2") (pin "3") (pinfunction "S_3") (pintype "passive"))
      (node (ref "U$1") (pin "1") (pinfunction "SOURCE1_1") (pintype "bidirectional"))
    )
    (net (code "35") (name "Net-(U$1-SOURCE2)") (class "Default")
      (node (ref "C6") (pin "1") (pinfunction "1_1") (pintype "passive"))
      (node (ref "Q3") (pin "1") (pinfunction "S_1") (pintype "passive"))
      (node (ref "Q3") (pin "2") (pinfunction "S_2") (pintype "passive"))
      (node (ref "Q3") (pin "3") (pinfunction "S_3") (pintype "passive"))
      (node (ref "Q4") (pin "1") (pinfunction "S_1") (pintype "passive"))
      (node (ref "Q4") (pin "2") (pinfunction "S_2") (pintype "passive"))
      (node (ref "Q4") (pin "3") (pinfunction "S_3") (pintype "passive"))
      (node (ref "U$1") (pin "28") (pinfunction "SOURCE2_28") (pintype "bidirectional"))
    )
    (net (code "36") (name "Net-(U$1-TMR1)") (class "Default")
      (node (ref "C2") (pin "1") (pinfunction "1_1") (pintype "passive"))
      (node (ref "U$1") (pin "7") (pinfunction "TMR1_7") (pintype "bidirectional"))
    )
    (net (code "37") (name "Net-(U$1-TMR2)") (class "Default")
      (node (ref "C3") (pin "1") (pinfunction "1_1") (pintype "passive"))
      (node (ref "U$1") (pin "22") (pinfunction "TMR2_22") (pintype "bidirectional"))
    )
    (net (code "38") (name "Net-(U$1-UVF1)") (class "Default")
      (node (ref "R3") (pin "2") (pinfunction "2_2") (pintype "passive"))
      (node (ref "R4") (pin "1") (pinfunction "1_1") (pintype "passive"))
      (node (ref "U$1") (pin "4") (pinfunction "UVF1_4") (pintype "bidirectional"))
    )
    (net (code "39") (name "Net-(U$1-UVF2)") (class "Default")
      (node (ref "R7") (pin "2") (pinfunction "2_2") (pintype "passive"))
      (node (ref "R8") (pin "1") (pinfunction "1_1") (pintype "passive"))
      (node (ref "U$1") (pin "25") (pinfunction "UVF2_25") (pintype "bidirectional"))
    )
    (net (code "40") (name "Net-(U$1-UVR1)") (class "Default")
      (node (ref "R2") (pin "2") (pinfunction "2_2") (pintype "passive"))
      (node (ref "R3") (pin "1") (pinfunction "1_1") (pintype "passive"))
      (node (ref "U$1") (pin "5") (pinfunction "UVR1_5") (pintype "bidirectional"))
    )
    (net (code "41") (name "Net-(U$1-UVR2)") (class "Default")
      (node (ref "R6") (pin "2") (pinfunction "2_2") (pintype "passive"))
      (node (ref "R7") (pin "1") (pinfunction "1_1") (pintype "passive"))
      (node (ref "U$1") (pin "24") (pinfunction "UVR2_24") (pintype "bidirectional"))
    )
    (net (code "42") (name "Net-(U2-BOOT)") (class "Default")
      (node (ref "C16") (pin "1") (pinfunction "1_1") (pintype "passive"))
      (node (ref "U2") (pin "7") (pinfunction "BOOT_7") (pintype "bidirectional"))
    )
    (net (code "43") (name "Net-(U2-FB)") (class "Default")
      (node (ref "C20") (pin "1") (pinfunction "1_1") (pintype "passive"))
      (node (ref "R35") (pin "1") (pinfunction "1_1") (pintype "passive"))
      (node (ref "R36") (pin "1") (pinfunction "1_1") (pintype "passive"))
      (node (ref "U2") (pin "5") (pinfunction "FB_5") (pintype "bidirectional"))
    )
    (net (code "44") (name "Net-(U2-VCC)") (class "Default")
      (node (ref "C15") (pin "1") (pinfunction "1_1") (pintype "passive"))
      (node (ref "U2") (pin "6") (pinfunction "VCC_6") (pintype "bidirectional"))
    )
    (net (code "45") (name "RETRY") (class "Default")
      (node (ref "R28") (pin "2") (pinfunction "2_2") (pintype "passive"))
      (node (ref "S1") (pin "8") (pinfunction "8_8") (pintype "passive"))
      (node (ref "SV2") (pin "3") (pinfunction "3_3") (pintype "passive"))
      (node (ref "SW1") (pin "8") (pinfunction "8_8") (pintype "passive"))
      (node (ref "U$1") (pin "16") (pinfunction "RETRY_16") (pintype "bidirectional"))
    )
    (net (code "46") (name "STATUS_CH1") (class "Default")
      (node (ref "CH1") (pin "C") (pinfunction "C_C") (pintype "passive"))
      (node (ref "R31") (pin "2") (pinfunction "2_2") (pintype "passive"))
      (node (ref "SV1") (pin "8") (pinfunction "8_8") (pintype "passive"))
      (node (ref "U$1") (pin "9") (pinfunction "~{CH1}_9") (pintype "bidirectional"))
    )
    (net (code "47") (name "STATUS_CH2") (class "Default")
      (node (ref "CH2") (pin "C") (pinfunction "C_C") (pintype "passive"))
      (node (ref "R32") (pin "2") (pinfunction "2_2") (pintype "passive"))
      (node (ref "SV2") (pin "6") (pinfunction "6_6") (pintype "passive"))
      (node (ref "U$1") (pin "20") (pinfunction "~{CH2}_20") (pintype "bidirectional"))
    )
    (net (code "48") (name "STATUS_FAULT_CH1") (class "Default")
      (node (ref "FLT2") (pin "C") (pinfunction "C_C") (pintype "passive"))
      (node (ref "R30") (pin "2") (pinfunction "2_2") (pintype "passive"))
      (node (ref "S2") (pin "6") (pinfunction "6_6") (pintype "passive"))
      (node (ref "SV2") (pin "1") (pinfunction "1_1") (pintype "passive"))
      (node (ref "SW2") (pin "6") (pinfunction "6_6") (pintype "passive"))
      (node (ref "U$1") (pin "11") (pinfunction "~{FAULT1}_11") (pintype "bidirectional"))
    )
    (net (code "49") (name "STATUS_FAULT_CH2") (class "Default")
      (node (ref "FLT1") (pin "C") (pinfunction "C_C") (pintype "passive"))
      (node (ref "R29") (pin "2") (pinfunction "2_2") (pintype "passive"))
      (node (ref "S2") (pin "5") (pinfunction "5_5") (pintype "passive"))
      (node (ref "SV2") (pin "7") (pinfunction "7_7") (pintype "passive"))
      (node (ref "SW2") (pin "5") (pinfunction "5_5") (pintype "passive"))
      (node (ref "U$1") (pin "18") (pinfunction "~{FAULT2}_18") (pintype "bidirectional"))
    )
    (net (code "50") (name "STATUS_PGOOD_CH1") (class "Default")
      (node (ref "PG1") (pin "C") (pinfunction "C_C") (pintype "passive"))
      (node (ref "R33") (pin "2") (pinfunction "2_2") (pintype "passive"))
      (node (ref "SV1") (pin "6") (pinfunction "6_6") (pintype "passive"))
      (node (ref "U$1") (pin "10") (pinfunction "~{VALID1}_10") (pintype "bidirectional"))
    )
    (net (code "51") (name "STATUS_PGOOD_CH2") (class "Default")
      (node (ref "PG2") (pin "C") (pinfunction "C_C") (pintype "passive"))
      (node (ref "R34") (pin "2") (pinfunction "2_2") (pintype "passive"))
      (node (ref "SV2") (pin "4") (pinfunction "4_4") (pintype "passive"))
      (node (ref "U$1") (pin "19") (pinfunction "~{VALID2}_19") (pintype "bidirectional"))
    )
    (net (code "52") (name "VIN1") (class "Default")
      (node (ref "D1") (pin "C") (pinfunction "C_C") (pintype "passive"))
      (node (ref "D3") (pin "A") (pinfunction "A_A") (pintype "passive"))
      (node (ref "LED1") (pin "A") (pinfunction "A_A") (pintype "passive"))
      (node (ref "Q1") (pin "5") (pinfunction "D_5") (pintype "passive"))
      (node (ref "Q1") (pin "6") (pinfunction "D_6") (pintype "passive"))
      (node (ref "Q1") (pin "7") (pinfunction "D_7") (pintype "passive"))
      (node (ref "Q1") (pin "8") (pinfunction "D_8") (pintype "passive"))
      (node (ref "Q1") (pin "TH") (pinfunction "D_TH") (pintype "passive"))
      (node (ref "R4") (pin "2") (pinfunction "2_2") (pintype "passive"))
      (node (ref "R9") (pin "2") (pinfunction "2_2") (pintype "passive"))
      (node (ref "U$1") (pin "3") (pinfunction "V1_3") (pintype "bidirectional"))
      (node (ref "X2") (pin "10") (pinfunction "KL_10") (pintype "passive"))
      (node (ref "X2") (pin "11") (pinfunction "KL_11") (pintype "passive"))
    )
    (net (code "53") (name "VIN2") (class "Default")
      (node (ref "D2") (pin "C") (pinfunction "C_C") (pintype "passive"))
      (node (ref "D4") (pin "A") (pinfunction "A_A") (pintype "passive"))
      (node (ref "LED3") (pin "A") (pinfunction "A_A") (pintype "passive"))
      (node (ref "Q4") (pin "5") (pinfunction "D_5") (pintype "passive"))
      (node (ref "Q4") (pin "6") (pinfunction "D_6") (pintype "passive"))
      (node (ref "Q4") (pin "7") (pinfunction "D_7") (pintype "passive"))
      (node (ref "Q4") (pin "8") (pinfunction "D_8") (pintype "passive"))
      (node (ref "Q4") (pin "TH") (pinfunction "D_TH") (pintype "passive"))
      (node (ref "R12") (pin "2") (pinfunction "2_2") (pintype "passive"))
      (node (ref "R8") (pin "2") (pinfunction "2_2") (pintype "passive"))
      (node (ref "U$1") (pin "26") (pinfunction "V2_26") (pintype "bidirectional"))
      (node (ref "X2") (pin "2") (pinfunction "KL_2") (pintype "passive"))
      (node (ref "X2") (pin "3") (pinfunction "KL_3") (pintype "passive"))
    )
    (net (code "54") (name "VOUT") (class "Default")
      (node (ref "C10") (pin "1") (pinfunction "1_1") (pintype "passive"))
      (node (ref "C11") (pin "+") (pinfunction "+_+") (pintype "passive"))
      (node (ref "C12") (pin "+") (pinfunction "+_+") (pintype "passive"))
      (node (ref "C13") (pin "1") (pinfunction "1_1") (pintype "passive"))
      (node (ref "C14") (pin "1") (pinfunction "1_1") (pintype "passive"))
      (node (ref "C7") (pin "1") (pinfunction "1_1") (pintype "passive"))
      (node (ref "LED2") (pin "A") (pinfunction "A_A") (pintype "passive"))
      (node (ref "R10") (pin "2") (pinfunction "2_2") (pintype "passive"))
      (node (ref "R11") (pin "1") (pinfunction "1_1") (pintype "passive"))
      (node (ref "U$1") (pin "30") (pinfunction "OUT2_30") (pintype "bidirectional"))
      (node (ref "U$1") (pin "32") (pinfunction "EXTVCC_32") (pintype "bidirectional"))
      (node (ref "U$1") (pin "34") (pinfunction "CPOREF_34") (pintype "bidirectional"))
      (node (ref "U$1") (pin "35") (pinfunction "OUT1_35") (pintype "bidirectional"))
      (node (ref "U2") (pin "2") (pinfunction "VIN_2") (pintype "bidirectional"))
      (node (ref "U2") (pin "3") (pinfunction "EN_3") (pintype "bidirectional"))
      (node (ref "X2") (pin "6") (pinfunction "KL_6") (pintype "passive"))
      (node (ref "X2") (pin "7") (pinfunction "KL_7") (pintype "passive"))
    )
    (net (code "55") (name "unconnected-(S2-Pad1)") (class "Default")
      (node (ref "S2") (pin "1") (pinfunction "1_1") (pintype "passive"))
    )
    (net (code "56") (name "unconnected-(S2-Pad2)") (class "Default")
      (node (ref "S2") (pin "2") (pinfunction "2_2") (pintype "passive"))
    )
    (net (code "57") (name "unconnected-(S2-Pad7)") (class "Default")
      (node (ref "S2") (pin "7") (pinfunction "7_7") (pintype "passive"))
    )
    (net (code "58") (name "unconnected-(S2-Pad8)") (class "Default")
      (node (ref "S2") (pin "8") (pinfunction "8_8") (pintype "passive"))
    )
    (net (code "59") (name "unconnected-(SW2-Pad1)") (class "Default")
      (node (ref "SW2") (pin "1") (pinfunction "1_1") (pintype "passive"))
    )
    (net (code "60") (name "unconnected-(SW2-Pad2)") (class "Default")
      (node (ref "SW2") (pin "2") (pinfunction "2_2") (pintype "passive"))
    )
    (net (code "61") (name "unconnected-(SW2-Pad7)") (class "Default")
      (node (ref "SW2") (pin "7") (pinfunction "7_7") (pintype "passive"))
    )
    (net (code "62") (name "unconnected-(SW2-Pad8)") (class "Default")
      (node (ref "SW2") (pin "8") (pinfunction "8_8") (pintype "passive"))
    )
    (net (code "63") (name "unconnected-(U$1-CASOUT-Pad14)") (class "Default")
      (node (ref "U$1") (pin "14") (pinfunction "CASOUT_14") (pintype "bidirectional"))
    )
    (net (code "64") (name "unconnected-(U2-PG-Pad4)") (class "Default")
      (node (ref "U2") (pin "4") (pinfunction "PG_4") (pintype "bidirectional"))
    )
  )
)
